# Sheet1.net
KiCad netlist of a schematic drawn in Altium Designer
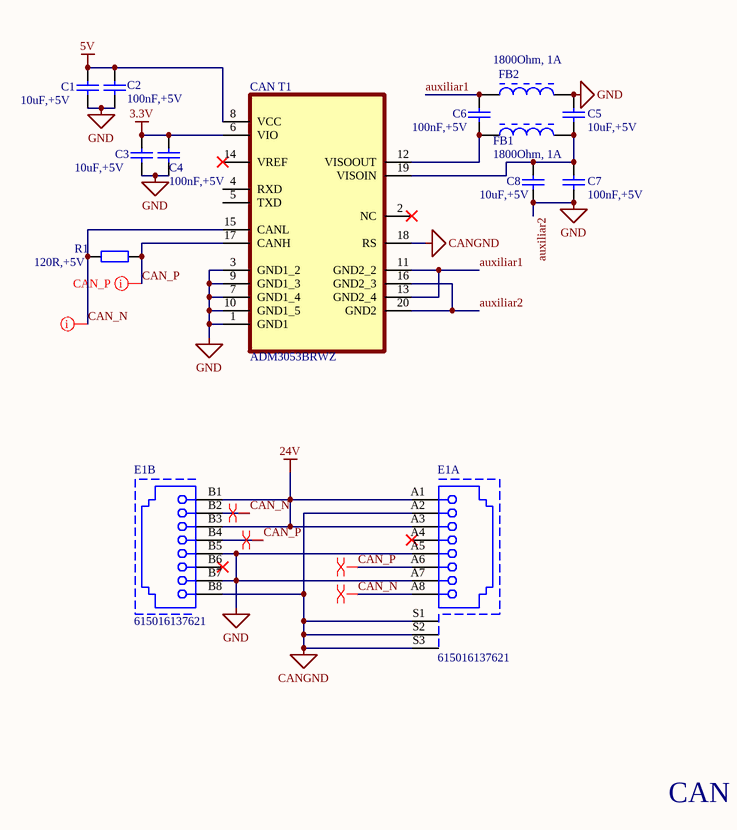
[diagram p0: Sheet1.SchDoc]

(export (version "E")
  (design (tool "Eeschema 10.0.6"))
  (components
    (comp (ref "C1")
      (value "10uF,+5V")
      (footprint "WCAP-CSGP_0805_H=1.25mm")
      (description "WCAP-CSGP Multilayer Ceramic Chip Capacitor, General Purpose, size 0805, X7R, 47nF, 100V")
      (fields
        (field (name "MANUFACTURER PART NUMBER") "885012207126")
        (field (name "MANUFACTURER") "Wurth Elektronik")
      )
      (libsource (lib "TelemetriaV2") (part "885012207126_7"))
    )
    (comp (ref "C2")
      (value "100nF,+5V")
      (footprint "WCAP-CSGP_1206_H=1.15mm")
      (description "WCAP-CSGP General Purpose Ceramic Capacitors, size 1206, 1uF, +/-10%, 10VDC")
      (fields (field (name "PART NUMBER") "885012208013") (field (name "PUBLISHER") "Wurth Elektronik"))
      (libsource (lib "TelemetriaV2") (part "885012208013_4"))
    )
    (comp (ref "C3")
      (value "10uF,+5V")
      (footprint "WCAP-CSGP_0805_H=1.25mm")
      (description "WCAP-CSGP Multilayer Ceramic Chip Capacitor, General Purpose, size 0805, X7R, 47nF, 100V")
      (fields
        (field (name "MANUFACTURER PART NUMBER") "885012207126")
        (field (name "MANUFACTURER") "Wurth Elektronik")
      )
      (libsource (lib "TelemetriaV2") (part "885012207126_7"))
    )
    (comp (ref "C4")
      (value "100nF,+5V")
      (footprint "WCAP-CSGP_1206_H=1.15mm")
      (description "WCAP-CSGP General Purpose Ceramic Capacitors, size 1206, 1uF, +/-10%, 10VDC")
      (fields (field (name "PART NUMBER") "885012208013") (field (name "PUBLISHER") "Wurth Elektronik"))
      (libsource (lib "TelemetriaV2") (part "885012208013_4"))
    )
    (comp (ref "C5")
      (value "10uF,+5V")
      (footprint "WCAP-CSGP_0805_H=1.25mm")
      (description "WCAP-CSGP Multilayer Ceramic Chip Capacitor, General Purpose, size 0805, X7R, 47nF, 100V")
      (fields
        (field (name "MANUFACTURER PART NUMBER") "885012207126")
        (field (name "MANUFACTURER") "Wurth Elektronik")
      )
      (libsource (lib "TelemetriaV2") (part "885012207126_7"))
    )
    (comp (ref "C6")
      (value "100nF,+5V")
      (footprint "WCAP-CSGP_1206_H=1.15mm")
      (description "WCAP-CSGP General Purpose Ceramic Capacitors, size 1206, 1uF, +/-10%, 10VDC")
      (fields (field (name "PART NUMBER") "885012208013") (field (name "PUBLISHER") "Wurth Elektronik"))
      (libsource (lib "TelemetriaV2") (part "885012208013_4"))
    )
    (comp (ref "C7")
      (value "100nF,+5V")
      (footprint "WCAP-CSGP_1206_H=1.15mm")
      (description "WCAP-CSGP General Purpose Ceramic Capacitors, size 1206, 1uF, +/-10%, 10VDC")
      (fields (field (name "PART NUMBER") "885012208013") (field (name "PUBLISHER") "Wurth Elektronik"))
      (libsource (lib "TelemetriaV2") (part "885012208013_4"))
    )
    (comp (ref "C8")
      (value "10uF,+5V")
      (footprint "WCAP-CSGP_0805_H=1.25mm")
      (description "WCAP-CSGP Multilayer Ceramic Chip Capacitor, General Purpose, size 0805, X7R, 47nF, 100V")
      (fields
        (field (name "MANUFACTURER PART NUMBER") "885012207126")
        (field (name "MANUFACTURER") "Wurth Elektronik")
      )
      (libsource (lib "TelemetriaV2") (part "885012207126_7"))
    )
    (comp (ref "CAN T1")
      (value "ADM3053BRWZ")
      (footprint "SOIC127P1032X265-20N")
      (description "DGT ISOL 2500VRMS 2CH CAN 20SOIC")
      (fields (field (name "MF") "Analog Devices"))
      (libsource (lib "TelemetriaV2") (part "ADM3053BRWZ"))
    )
    (comp (ref "E1")
      (value "615016137621")
      (footprint "615016137621")
      (description "WR-MJ Modular Jack THT Horizontal Shielded Dual Port 8P8C Tab Down")
      (fields (field (name "PUBLISHER") "Wurth Elektronik"))
      (libsource (lib "TelemetriaV2") (part "615016137621"))
    )
    (comp (ref "FB1")
      (value "1800Ohm, 1A")
      (footprint "WE-CBF_0805_Wide Band")
      (description "WE-CBF SMT EMI Suppression Ferrite Bead, size 0805, 1800Ohm, 1A")
      (fields
        (field (name "MANUFACTURER PART NUMBER") "742792090")
        (field (name "MANUFACTURER") "Wurth Elektronik")
      )
      (libsource (lib "TelemetriaV2") (part "742792090"))
    )
    (comp (ref "FB2")
      (value "1800Ohm, 1A")
      (footprint "WE-CBF_0805_Wide Band")
      (description "WE-CBF SMT EMI Suppression Ferrite Bead, size 0805, 1800Ohm, 1A")
      (fields
        (field (name "MANUFACTURER PART NUMBER") "742792090")
        (field (name "MANUFACTURER") "Wurth Elektronik")
      )
      (libsource (lib "TelemetriaV2") (part "742792090"))
    )
    (comp (ref "R1")
      (value "120R,+5V")
      (footprint "WRIS-KSKE_0805")
      (description "WRIS-KSKE SMT Thick Film Resistor, size 0805, 1Ohm, 0.33W")
      (fields
        (field (name "MANUFACTURER") "Wurth Elektronik")
        (field (name "MANUFACTURER PART NUMBER") "560050320011")
      )
      (libsource (lib "TelemetriaV2") (part "560050320011_9"))
    )
  )
  (nets
    (net (code "1") (name "/CAN_N") (class "Default")
      (node (ref "CAN T1") (pin "15") (pinfunction "CANL_15") (pintype "passive"))
      (node (ref "E1") (pin "A8") (pinfunction "A8_A8") (pintype "passive"))
      (node (ref "E1") (pin "B2") (pinfunction "B2_B2") (pintype "passive"))
      (node (ref "R1") (pin "1") (pinfunction "1_1") (pintype "passive"))
    )
    (net (code "2") (name "/CAN_P") (class "Default")
      (node (ref "CAN T1") (pin "17") (pinfunction "CANH_17") (pintype "passive"))
      (node (ref "E1") (pin "A6") (pinfunction "A6_A6") (pintype "passive"))
      (node (ref "E1") (pin "B4") (pinfunction "B4_B4") (pintype "passive"))
      (node (ref "R1") (pin "2") (pinfunction "2_2") (pintype "passive"))
    )
    (net (code "3") (name "/auxiliar1") (class "Default")
      (node (ref "C6") (pin "2") (pinfunction "2_2") (pintype "passive"))
      (node (ref "CAN T1") (pin "11") (pinfunction "GND2_2_11") (pintype "passive"))
      (node (ref "CAN T1") (pin "13") (pinfunction "GND2_4_13") (pintype "passive"))
      (node (ref "FB2") (pin "1") (pinfunction "1_1") (pintype "passive"))
    )
    (net (code "4") (name "3.3V") (class "Default")
      (node (ref "C3") (pin "2") (pinfunction "2_2") (pintype "passive"))
      (node (ref "C4") (pin "2") (pinfunction "2_2") (pintype "passive"))
      (node (ref "CAN T1") (pin "6") (pinfunction "VIO_6") (pintype "passive"))
    )
    (net (code "5") (name "5V") (class "Default")
      (node (ref "C1") (pin "2") (pinfunction "2_2") (pintype "passive"))
      (node (ref "C2") (pin "2") (pinfunction "2_2") (pintype "passive"))
      (node (ref "CAN T1") (pin "8") (pinfunction "VCC_8") (pintype "passive"))
    )
    (net (code "6") (name "24V") (class "Default")
      (node (ref "E1") (pin "A1") (pinfunction "A1_A1") (pintype "passive"))
      (node (ref "E1") (pin "A3") (pinfunction "A3_A3") (pintype "passive"))
      (node (ref "E1") (pin "B1") (pinfunction "B1_B1") (pintype "passive"))
      (node (ref "E1") (pin "B3") (pinfunction "B3_B3") (pintype "passive"))
    )
    (net (code "7") (name "CANGND") (class "Default")
      (node (ref "CAN T1") (pin "18") (pinfunction "RS_18") (pintype "passive"))
      (node (ref "E1") (pin "A2") (pinfunction "A2_A2") (pintype "passive"))
      (node (ref "E1") (pin "B8") (pinfunction "B8_B8") (pintype "passive"))
      (node (ref "E1") (pin "S1") (pinfunction "S1_S1") (pintype "passive"))
      (node (ref "E1") (pin "S2") (pinfunction "S2_S2") (pintype "passive"))
      (node (ref "E1") (pin "S3") (pinfunction "S3_S3") (pintype "passive"))
    )
    (net (code "8") (name "GND") (class "Default")
      (node (ref "C1") (pin "1") (pinfunction "1_1") (pintype "passive"))
      (node (ref "C2") (pin "1") (pinfunction "1_1") (pintype "passive"))
      (node (ref "C3") (pin "1") (pinfunction "1_1") (pintype "passive"))
      (node (ref "C4") (pin "1") (pinfunction "1_1") (pintype "passive"))
      (node (ref "C5") (pin "2") (pinfunction "2_2") (pintype "passive"))
      (node (ref "C7") (pin "1") (pinfunction "1_1") (pintype "passive"))
      (node (ref "C8") (pin "1") (pinfunction "1_1") (pintype "passive"))
      (node (ref "CAN T1") (pin "1") (pinfunction "GND1_1") (pintype "passive"))
      (node (ref "CAN T1") (pin "10") (pinfunction "GND1_5_10") (pintype "passive"))
      (node (ref "CAN T1") (pin "16") (pinfunction "GND2_3_16") (pintype "passive"))
      (node (ref "CAN T1") (pin "20") (pinfunction "GND2_20") (pintype "passive"))
      (node (ref "CAN T1") (pin "3") (pinfunction "GND1_2_3") (pintype "passive"))
      (node (ref "CAN T1") (pin "7") (pinfunction "GND1_4_7") (pintype "passive"))
      (node (ref "CAN T1") (pin "9") (pinfunction "GND1_3_9") (pintype "passive"))
      (node (ref "E1") (pin "A5") (pinfunction "A5_A5") (pintype "passive"))
      (node (ref "E1") (pin "A7") (pinfunction "A7_A7") (pintype "passive"))
      (node (ref "E1") (pin "B5") (pinfunction "B5_B5") (pintype "passive"))
      (node (ref "E1") (pin "B7") (pinfunction "B7_B7") (pintype "passive"))
      (node (ref "FB2") (pin "2") (pinfunction "2_2") (pintype "passive"))
    )
    (net (code "9") (name "Net-(CAN T1-VISOIN)") (class "Default")
      (node (ref "C5") (pin "1") (pinfunction "1_1") (pintype "passive"))
      (node (ref "C7") (pin "2") (pinfunction "2_2") (pintype "passive"))
      (node (ref "C8") (pin "2") (pinfunction "2_2") (pintype "passive"))
      (node (ref "CAN T1") (pin "19") (pinfunction "VISOIN_19") (pintype "passive"))
      (node (ref "FB1") (pin "2") (pinfunction "2_2") (pintype "passive"))
    )
    (net (code "10") (name "Net-(CAN T1-VISOOUT)") (class "Default")
      (node (ref "C6") (pin "1") (pinfunction "1_1") (pintype "passive"))
      (node (ref "CAN T1") (pin "12") (pinfunction "VISOOUT_12") (pintype "passive"))
      (node (ref "FB1") (pin "1") (pinfunction "1_1") (pintype "passive"))
    )
    (net (code "11") (name "unconnected-(CAN T1-NC-Pad2)") (class "Default")
      (node (ref "CAN T1") (pin "2") (pinfunction "NC_2") (pintype "passive+no_connect"))
    )
    (net (code "12") (name "unconnected-(CAN T1-RXD-Pad4)") (class "Default")
      (node (ref "CAN T1") (pin "4") (pinfunction "RXD_4") (pintype "passive"))
    )
    (net (code "13") (name "unconnected-(CAN T1-TXD-Pad5)") (class "Default")
      (node (ref "CAN T1") (pin "5") (pinfunction "TXD_5") (pintype "passive"))
    )
    (net (code "14") (name "unconnected-(CAN T1-VREF-Pad14)") (class "Default")
      (node (ref "CAN T1") (pin "14") (pinfunction "VREF_14") (pintype "passive+no_connect"))
    )
    (net (code "15") (name "unconnected-(E1-PadA4)") (class "Default")
      (node (ref "E1") (pin "A4") (pinfunction "A4_A4") (pintype "passive+no_connect"))
    )
    (net (code "16") (name "unconnected-(E1-PadB6)") (class "Default")
      (node (ref "E1") (pin "B6") (pinfunction "B6_B6") (pintype "passive+no_connect"))
    )
  )
)
